# jlin_transceiver_prototype.net
KiCad netlist of a schematic drawn in Altium Designer
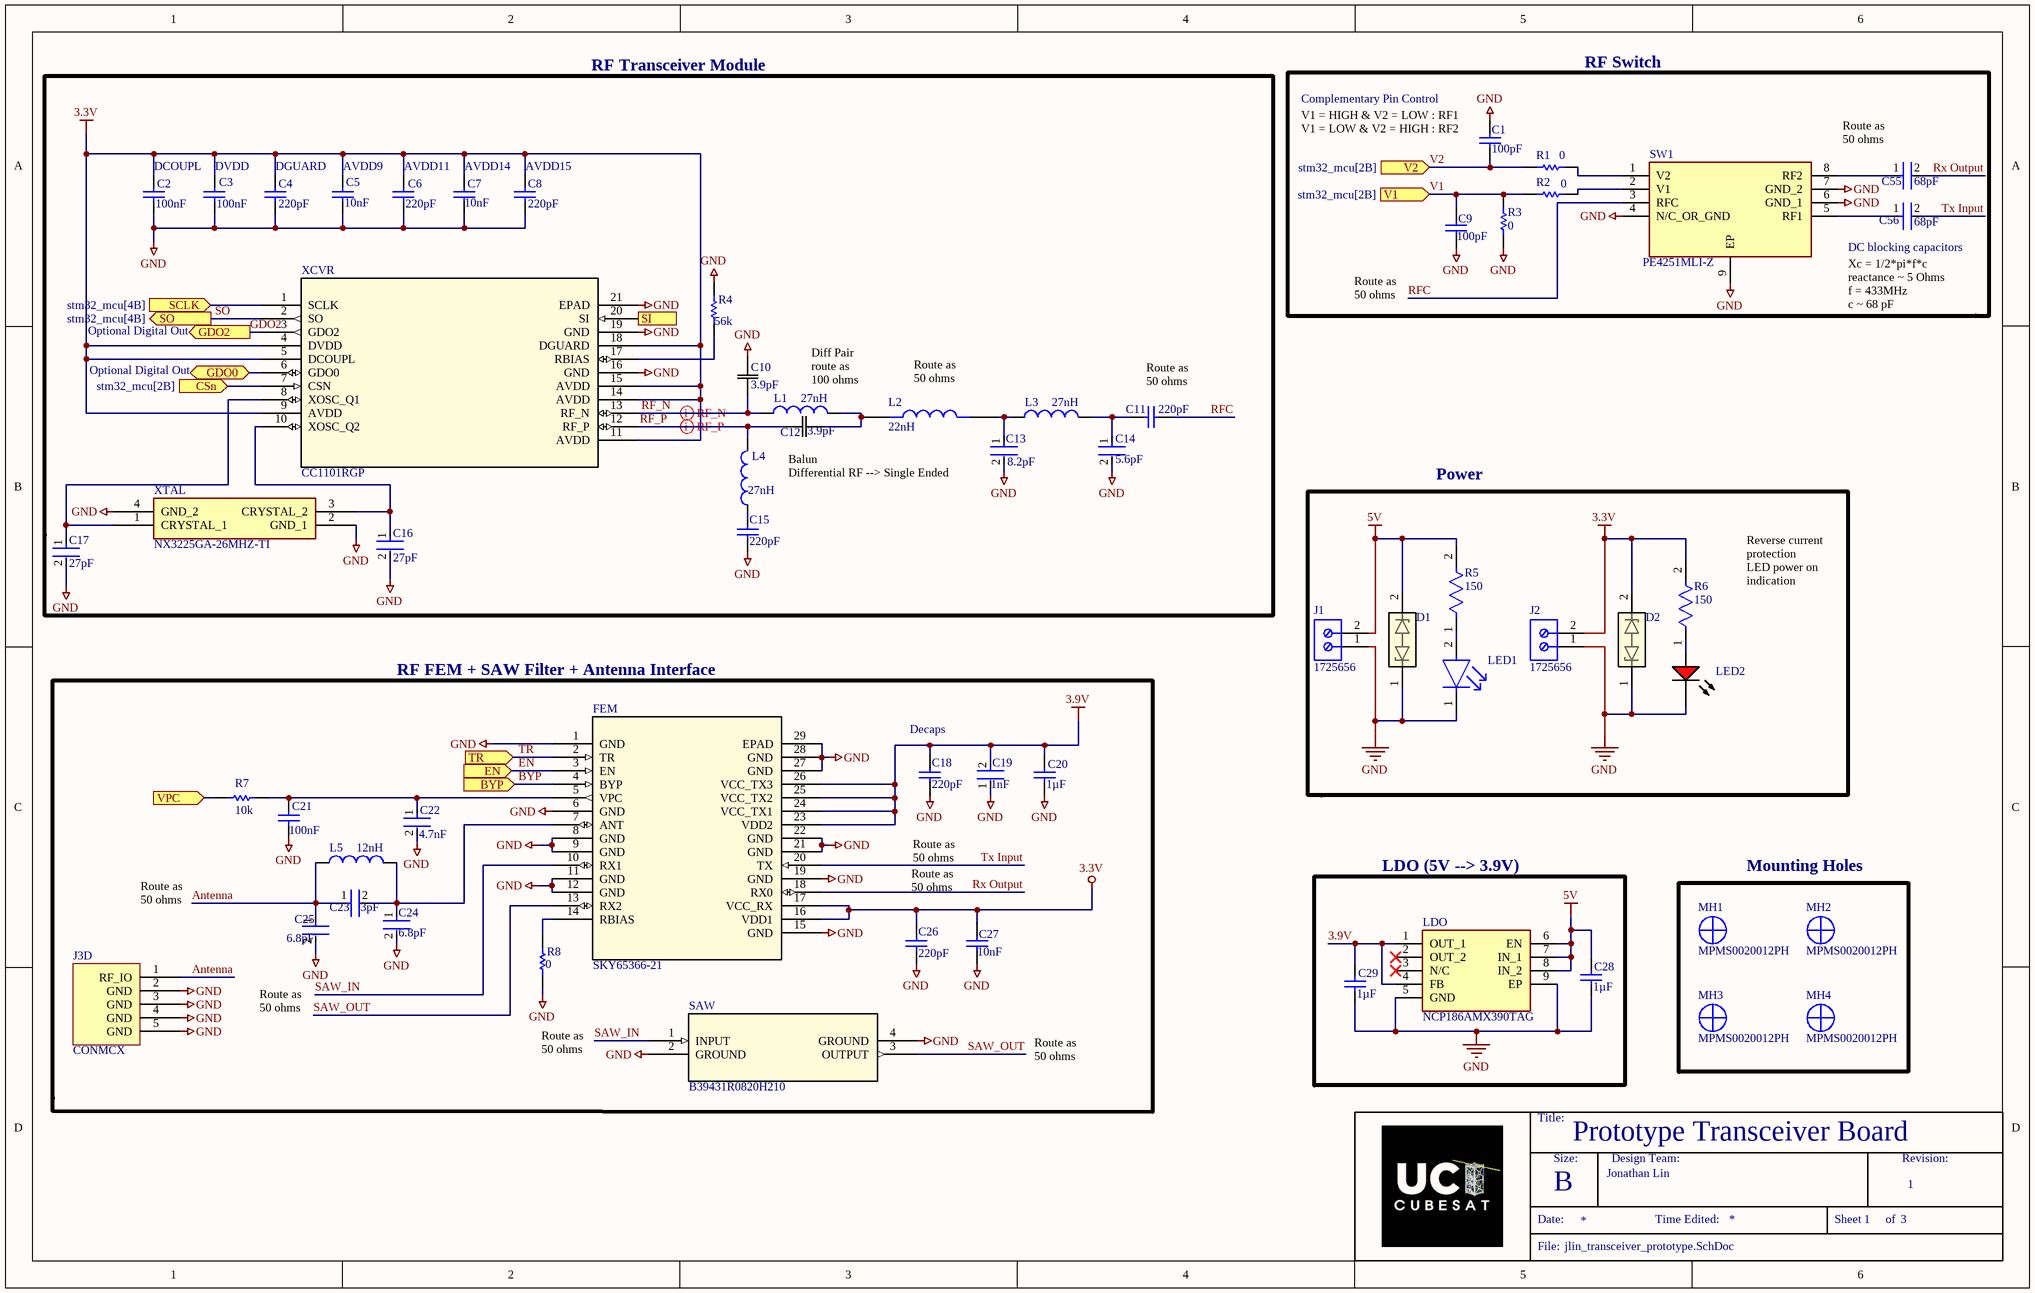
[diagram p0: jlin_transceiver_prototype.SchDoc]

(export (version "E")
  (design (tool "Eeschema 10.0.6"))
  (components
    (comp (ref "C1")
      (value "100pF")
      (footprint "CAPC2013X70X45LL10T25")
      (fields (field (name "Comment") "GRM2165C1H101JA01D"))
      (libsource (lib "University of California Irvine") (part "CAP"))
    )
    (comp (ref "C2")
      (value "100nF")
      (footprint "CAPC2013X135X45ML10T25")
      (fields (field (name "Comment") "GRM21BR72A104KAC4L"))
      (libsource (lib "University of California Irvine") (part "CAP"))
    )
    (comp (ref "C3")
      (value "100nF")
      (footprint "CAPC2013X135X45ML10T25")
      (fields (field (name "Comment") "GRM21BR72A104KAC4L"))
      (libsource (lib "University of California Irvine") (part "CAP"))
    )
    (comp (ref "C4")
      (value "220pF")
      (footprint "CAPC2013X70X45LL10T25")
      (fields (field (name "Comment") "GRM2165C1H221JA01D"))
      (libsource (lib "University of California Irvine") (part "CAP"))
    )
    (comp (ref "C5")
      (value "10nF")
      (footprint "CAPC2013X135X45ML10T25")
      (fields (field (name "Comment") "GRM21BR72A103KA01K"))
      (libsource (lib "University of California Irvine") (part "CAP"))
    )
    (comp (ref "C6")
      (value "220pF")
      (footprint "CAPC2013X70X45LL10T25")
      (fields (field (name "Comment") "GRM2165C1H221JA01D"))
      (libsource (lib "University of California Irvine") (part "CAP"))
    )
    (comp (ref "C7")
      (value "10nF")
      (footprint "CAPC2013X135X45ML10T25")
      (fields (field (name "Comment") "GRM21BR72A103KA01K"))
      (libsource (lib "University of California Irvine") (part "CAP"))
    )
    (comp (ref "C8")
      (value "220pF")
      (footprint "CAPC2013X70X45LL10T25")
      (fields (field (name "Comment") "GRM2165C1H221JA01D"))
      (libsource (lib "University of California Irvine") (part "CAP"))
    )
    (comp (ref "C9")
      (value "100pF")
      (footprint "CAPC2013X70X45LL10T25")
      (fields (field (name "Comment") "GRM2165C1H101JA01D"))
      (libsource (lib "University of California Irvine") (part "CAP"))
    )
    (comp (ref "C10")
      (value "3.9pF")
      (footprint "CAP_CC0805_YAG")
      (description "3.9 pF ±0.25pF 50V Ceramic Capacitor C0G, NP0 0805 (2012 Metric)")
      (fields (field (name "Comment") "CC0805CRNPO9BN3R9"))
      (libsource (lib "University of California Irvine") (part "CC0805CRNPO9BN3R9"))
    )
    (comp (ref "C11")
      (value "220pF")
      (footprint "CAPC2013X70X45LL10T25")
      (fields (field (name "Comment") "GRM2165C1H221JA01D"))
      (libsource (lib "University of California Irvine") (part "CAP"))
    )
    (comp (ref "C12")
      (value "3.9pF")
      (footprint "CAP_CC0805_YAG")
      (description "3.9 pF ±0.25pF 50V Ceramic Capacitor C0G, NP0 0805 (2012 Metric)")
      (fields (field (name "Comment") "CC0805CRNPO9BN3R9"))
      (libsource (lib "University of California Irvine") (part "CC0805CRNPO9BN3R9"))
    )
    (comp (ref "C13")
      (value "8.2pF")
      (footprint "FP-0805-L_2_01_0_2-W_1_25-MFG")
      (description "Cap Cer 8.2PF 100V C0G/NP0 0805")
      (fields (field (name "Comment") "KGM21BCG2A8R2DT"))
      (libsource (lib "University of California Irvine") (part "02cd4be3c70576c341d710602a673aa"))
    )
    (comp (ref "C14")
      (value "5.6pF")
      (footprint "FP-C0805C-DN-IPC_A")
      (fields (field (name "Comment") "C0805C569C5GACTU"))
      (libsource (lib "University of California Irvine") (part "b4654b650e69147ec39a6b967a45e02"))
    )
    (comp (ref "C15")
      (value "220pF")
      (footprint "CAPC2013X70X45LL10T25")
      (fields (field (name "Comment") "GRM2165C1H221JA01D"))
      (libsource (lib "University of California Irvine") (part "CAP"))
    )
    (comp (ref "C16")
      (value "27pF")
      (footprint "FP-GRM21A-0_2-IPC_B")
      (fields (field (name "Comment") "GRM21A5C2E270JW01D"))
      (libsource (lib "University of California Irvine") (part "02cd4be3c70576c341d710602a673aa"))
    )
    (comp (ref "C17")
      (value "27pF")
      (footprint "FP-GRM21A-0_2-IPC_B")
      (fields (field (name "Comment") "GRM21A5C2E270JW01D"))
      (libsource (lib "University of California Irvine") (part "02cd4be3c70576c341d710602a673aa"))
    )
    (comp (ref "C18")
      (value "220pF")
      (footprint "CAPC2013X70X45LL10T25")
      (fields (field (name "Comment") "GRM2165C1H221JA01D"))
      (libsource (lib "University of California Irvine") (part "CAP"))
    )
    (comp (ref "C19")
      (value "1nF")
      (footprint "FP-GRM216-0_1-IPC_B")
      (fields (field (name "Comment") "GRM2165C2A102JA01D"))
      (libsource (lib "University of California Irvine") (part "236180d848d6139a670b325ea6854c9"))
    )
    (comp (ref "C20")
      (value "1µF")
      (footprint "CAPC2013X135X45LL10T25")
      (fields (field (name "Comment") "GRM21BR71C105KA01L"))
      (libsource (lib "University of California Irvine") (part "CAP-NP-2"))
    )
    (comp (ref "C21")
      (value "100nF")
      (footprint "CAPC2013X135X45ML10T25")
      (fields (field (name "Comment") "GRM21BR72A104KAC4L"))
      (libsource (lib "University of California Irvine") (part "CAP"))
    )
    (comp (ref "C22")
      (value "4.7nF")
      (footprint "FP-GRM219-0_1-MFG")
      (fields (field (name "Comment") "GRM2195C1H472JA01D"))
      (libsource (lib "University of California Irvine") (part "02cd4be3c70576c341d710602a673aa"))
    )
    (comp (ref "C23")
      (value "3pF")
      (footprint "FP-C0805C-DN-IPC_A")
      (fields (field (name "Comment") "C0805C309C5GACTU"))
      (libsource (lib "University of California Irvine") (part "b4654b650e69147ec39a6b967a45e02"))
    )
    (comp (ref "C24")
      (value "6.8pF")
      (footprint "FP-GQM219-0_15-MFG")
      (fields (field (name "Comment") "GQM2195C2E6R8BB12D"))
      (libsource (lib "University of California Irvine") (part "b4654b650e69147ec39a6b967a45e02"))
    )
    (comp (ref "C25")
      (value "6.8pF")
      (footprint "FP-GQM219-0_15-MFG")
      (fields (field (name "Comment") "GQM2195C2E6R8BB12D"))
      (libsource (lib "University of California Irvine") (part "b4654b650e69147ec39a6b967a45e02"))
    )
    (comp (ref "C26")
      (value "220pF")
      (footprint "CAPC2013X70X45LL10T25")
      (fields (field (name "Comment") "GRM2165C1H221JA01D"))
      (libsource (lib "University of California Irvine") (part "CAP"))
    )
    (comp (ref "C27")
      (value "10nF")
      (footprint "CAPC2013X135X45ML10T25")
      (fields (field (name "Comment") "GRM21BR72A103KA01K"))
      (libsource (lib "University of California Irvine") (part "CAP"))
    )
    (comp (ref "C28")
      (value "1µF")
      (footprint "CAPC2013X135X45LL10T25")
      (fields (field (name "Comment") "GRM21BR71C105KA01L"))
      (libsource (lib "University of California Irvine") (part "CAP-NP-2"))
    )
    (comp (ref "C29")
      (value "1µF")
      (footprint "CAPC2013X135X45LL10T25")
      (fields (field (name "Comment") "GRM21BR71C105KA01L"))
      (libsource (lib "University of California Irvine") (part "CAP-NP-2"))
    )
    (comp (ref "C55")
      (value "68pF")
      (footprint "FP-GRM21A-0_2-IPC_B")
      (fields (field (name "Comment") "GRM21A5C2E680JW01D"))
      (libsource (lib "University of California Irvine") (part "02cd4be3c70576c341d710602a673aa"))
    )
    (comp (ref "C56")
      (value "68pF")
      (footprint "FP-GRM21A-0_2-IPC_B")
      (fields (field (name "Comment") "GRM21A5C2E680JW01D"))
      (libsource (lib "University of California Irvine") (part "02cd4be3c70576c341d710602a673aa"))
    )
    (comp (ref "D1")
      (value "PESD3V3Z1BCSFYL")
      (footprint "SOD962-2_DSN0603-2_NEX")
      (description "PESD3V3Zxx: 6.8 V 15 A 0.45 pF Bidirectional ESD Protection Diode - DSN0603-2")
      (libsource (lib "University of California Irvine") (part "PESD3V3Z1BCSFYL-Symbol-1"))
    )
    (comp (ref "D2")
      (value "PESD3V3Z1BCSFYL")
      (footprint "SOD962-2_DSN0603-2_NEX")
      (description "PESD3V3Zxx: 6.8 V 15 A 0.45 pF Bidirectional ESD Protection Diode - DSN0603-2")
      (libsource (lib "University of California Irvine") (part "PESD3V3Z1BCSFYL-Symbol-1"))
    )
    (comp (ref "FEM")
      (value "SKY65366-21")
      (footprint "SKY65366-21-Footprint-1")
      (description "RF and Baseband Circuit")
      (libsource (lib "Jonathan Lin") (part "SKY65366-21-Symbol-1"))
    )
    (comp (ref "J1")
      (value "1725656")
      (footprint "PHOE-1725656-2")
      (description "Male Header, Pitch 2.54 mm, 1 x 2 Position, Height 9 mm, Tail Length 3.5 mm")
      (fields (field (name "MANUFACTURER") "Phoenix Contact"))
      (libsource (lib "Altium Content Vault") (part "CN-1P-F-TB2"))
    )
    (comp (ref "J2")
      (value "1725656")
      (footprint "PHOE-1725656-2")
      (description "Male Header, Pitch 2.54 mm, 1 x 2 Position, Height 9 mm, Tail Length 3.5 mm")
      (fields (field (name "MANUFACTURER") "Phoenix Contact"))
      (libsource (lib "Altium Content Vault") (part "CN-1P-F-TB2"))
    )
    (comp (ref "J3")
      (value "CONMCX")
      (footprint "CONMCX002-Footprint-1")
      (description "MCX Connector Right Angle Jack (Female), PCB Through-Hole Mount, Gold")
      (libsource (lib "University of California Irvine") (part "CONMCX002-Symbol-1"))
    )
    (comp (ref "L1")
      (value "27nH")
      (footprint "WE-MK_0805_L2W1.25H0.85")
      (description "Multilayer Inductor, 27Nh, 0.3A, 0805 Rohs Compliant: Yes")
      (fields (field (name "Comment") "7447880127"))
      (libsource (lib "University of California Irvine") (part "Inductor - 1"))
    )
    (comp (ref "L2")
      (value "22nH")
      (footprint "INDC2012X105N")
      (description "General Purpose Inductor, 0.022uH, 5%, 1 Element, Ceramic-Core, SMD, 0805")
      (fields (field (name "MF") "Abracon") (field (name "MP") "AIMC-0805-22NJ-T"))
      (libsource (lib "University of California Irvine") (part "AIMC-0805-22NJ-T"))
    )
    (comp (ref "L3")
      (value "27nH")
      (footprint "WE-MK_0805_L2W1.25H0.85")
      (description "Multilayer Inductor, 27Nh, 0.3A, 0805 Rohs Compliant: Yes")
      (fields (field (name "Comment") "7447880127"))
      (libsource (lib "University of California Irvine") (part "Inductor - 1"))
    )
    (comp (ref "L4")
      (value "27nH")
      (footprint "WE-MK_0805_L2W1.25H0.85")
      (description "Multilayer Inductor, 27Nh, 0.3A, 0805 Rohs Compliant: Yes")
      (fields (field (name "Comment") "7447880127"))
      (libsource (lib "University of California Irvine") (part "Inductor - 1"))
    )
    (comp (ref "L5")
      (value "12nH")
      (footprint "AIMC-0805_ABR")
      (description "General Purpose Inductor, 0.012uH, 5%, 1 Element, Ceramic-Core, SMD, 0805")
      (fields (field (name "TOLERANCE") "5%") (field (name "Comment") "AIMC-0805-12NJ-T"))
      (libsource (lib "University of California Irvine") (part "IND-2"))
    )
    (comp (ref "LDO")
      (value "NCP186AMX390TAG")
      (footprint "NCP186AMX330TAG")
      (description "Fixed Positive LDO Regulator, 3.9V, 0.13V Dropout, CMOS, PDSO8")
      (fields (field (name "MOUSER PART NUMBER") "863-NCP186AMX390TAG"))
      (libsource (lib "University of California Irvine") (part "NCP186AMX390TAG"))
    )
    (comp (ref "LED1")
      (value "LTST-C170KFKT")
      (footprint "FP-LTST-C170KFKT-MFG")
      (description "Single Color LED, Orange, Water Clear, 1.4mm")
      (libsource (lib "University of California Irvine") (part "8706943c75ba83719d021d2fdc84c58"))
    )
    (comp (ref "LED2")
      (value "LTST-C190KRKT")
      (footprint "LTST-C191KRKT_V")
      (description "LED Uni-Color Red, 62.5 mW, 25 mA, -30 to 85 degC, 2-Pin SMD, RoHS, Tape and Reel")
      (fields (field (name "POWER") "75mW") (field (name "MANUFACTURER") "Lite-On"))
      (libsource (lib "University of California Irvine") (part "LED-RED-AK-2"))
    )
    (comp (ref "MH1")
      (value "MPMS0020012PH")
      (footprint "BF-MPMS0020012PH")
      (description "Copper Pillar, M2 Screw")
      (fields (field (name "MANUFACTURER") "B&F Fastener Supply"))
      (libsource (lib "University of California Irvine") (part "BF-MPMS0020012PH"))
    )
    (comp (ref "MH2")
      (value "MPMS0020012PH")
      (footprint "BF-MPMS0020012PH")
      (description "Copper Pillar, M2 Screw")
      (fields (field (name "MANUFACTURER") "B&F Fastener Supply"))
      (libsource (lib "University of California Irvine") (part "BF-MPMS0020012PH"))
    )
    (comp (ref "MH3")
      (value "MPMS0020012PH")
      (footprint "BF-MPMS0020012PH")
      (description "Copper Pillar, M2 Screw")
      (fields (field (name "MANUFACTURER") "B&F Fastener Supply"))
      (libsource (lib "University of California Irvine") (part "BF-MPMS0020012PH"))
    )
    (comp (ref "MH4")
      (value "MPMS0020012PH")
      (footprint "BF-MPMS0020012PH")
      (description "Copper Pillar, M2 Screw")
      (fields (field (name "MANUFACTURER") "B&F Fastener Supply"))
      (libsource (lib "University of California Irvine") (part "BF-MPMS0020012PH"))
    )
    (comp (ref "R1")
      (value "0")
      (footprint "RESC2013X60X35ML10T20")
      (description "Chip Resistor, 0 Ohm, 0.125 W, -55 to 155 degC, 0805 (2012 Metric)")
      (fields (field (name "POWER") "125mW") (field (name "TOLERANCE") "5%"))
      (libsource (lib "University of California Irvine") (part "RES-2"))
    )
    (comp (ref "R2")
      (value "0")
      (footprint "RESC2013X60X35ML10T20")
      (description "Chip Resistor, 0 Ohm, 0.125 W, -55 to 155 degC, 0805 (2012 Metric)")
      (fields (field (name "POWER") "125mW") (field (name "TOLERANCE") "5%"))
      (libsource (lib "University of California Irvine") (part "RES-2"))
    )
    (comp (ref "R3")
      (value "0")
      (footprint "RESC2013X60X35ML10T20")
      (description "Chip Resistor, 0 Ohm, 0.125 W, -55 to 155 degC, 0805 (2012 Metric)")
      (fields (field (name "POWER") "125mW") (field (name "TOLERANCE") "5%"))
      (libsource (lib "University of California Irvine") (part "RES-2"))
    )
    (comp (ref "R4")
      (value "56k")
      (footprint "RESC2013X70X40NL20T20")
      (fields
        (field (name "POWER") "125mW")
        (field (name "TOLERANCE") "5%")
        (field (name "Comment") "ERJ-6GEYJ563V")
      )
      (libsource (lib "University of California Irvine") (part "RES"))
    )
    (comp (ref "R5")
      (value "150")
      (footprint "FP-CRCW1210-e3-IPC_C")
      (fields
        (field (name "POWER") "500mW")
        (field (name "TOLERANCE") "5%")
        (field (name "Comment") "CRCW1210150RJNEA")
      )
      (libsource (lib "University of California Irvine") (part "1029c3af85768c4190bb7ad29bc67b5"))
    )
    (comp (ref "R6")
      (value "150")
      (footprint "FP-CRCW1210-e3-IPC_C")
      (fields
        (field (name "POWER") "500mW")
        (field (name "TOLERANCE") "5%")
        (field (name "Comment") "CRCW1210150RJNEA")
      )
      (libsource (lib "University of California Irvine") (part "1029c3af85768c4190bb7ad29bc67b5"))
    )
    (comp (ref "R7")
      (value "10k")
      (footprint "RESC2013X60X35LL10T20")
      (fields
        (field (name "TOLERANCE") "1%")
        (field (name "POWER") "125mW")
        (field (name "Comment") "RC0805FR-0710KL")
      )
      (libsource (lib "University of California Irvine") (part "RES-2"))
    )
    (comp (ref "R8")
      (value "0")
      (footprint "RESC2013X60X35ML10T20")
      (description "Chip Resistor, 0 Ohm, 0.125 W, -55 to 155 degC, 0805 (2012 Metric)")
      (fields (field (name "POWER") "125mW") (field (name "TOLERANCE") "5%"))
      (libsource (lib "University of California Irvine") (part "RES-2"))
    )
    (comp (ref "SAW")
      (value "B39431R0820H210")
      (footprint "B39431R0820H210_QUA")
      (description "433.92MHz SAW Resonator50 Ohm -40°C ~ 125°C Surface Mount")
      (libsource (lib "University of California Irvine") (part "B39431R0820H210-Symbol-1"))
    )
    (comp (ref "SW1")
      (value "PE4251MLI-Z")
      (footprint "SOP65P490X106-9N")
      (description "SPDT, 10MHz Min, 3000MHz Max, 1 Func, 0.9dB Insertion Loss-Max, CMOS")
      (fields (field (name "MOUSER PART NUMBER") "81-PE4251MLI-Z"))
      (libsource (lib "University of California Irvine") (part "PE4251MLI-Z"))
    )
    (comp (ref "XCVR")
      (value "CC1101RGP")
      (footprint "CC1101RGP-Footprint-1")
      (description "RF and Baseband Circuit, PQCC20")
      (libsource (lib "Jonathan Lin") (part "CC1101RGP-Symbol-1"))
    )
    (comp (ref "XTAL")
      (value "NX3225GA-26MHZ-TI")
      (footprint "NX3225GA_NDK")
      (description "Crystal 26.0000MHZ 10PF SMD")
      (libsource (lib "University of California Irvine") (part "NX3225GA-26MHZ-TI-Symbol-1"))
    )
  )
  (nets
    (net (code "1") (name "/Antenna") (class "Default")
      (node (ref "C23") (pin "1") (pinfunction "1_1") (pintype "passive"))
      (node (ref "C25") (pin "1") (pinfunction "1_1") (pintype "passive"))
      (node (ref "J3") (pin "1") (pinfunction "RF_IO_1") (pintype "passive"))
      (node (ref "L5") (pin "1") (pinfunction "1_1") (pintype "passive"))
    )
    (net (code "2") (name "/BYP") (class "Default")
      (node (ref "FEM") (pin "4") (pinfunction "BYP_4") (pintype "input"))
    )
    (net (code "3") (name "/CSn") (class "Default")
      (node (ref "XCVR") (pin "7") (pinfunction "CSN_7") (pintype "input"))
    )
    (net (code "4") (name "/EN") (class "Default")
      (node (ref "FEM") (pin "3") (pinfunction "EN_3") (pintype "input"))
    )
    (net (code "5") (name "/GDO0") (class "Default")
      (node (ref "XCVR") (pin "6") (pinfunction "GDO0_6") (pintype "bidirectional"))
    )
    (net (code "6") (name "/GDO2") (class "Default")
      (node (ref "XCVR") (pin "3") (pinfunction "GDO2_3") (pintype "output"))
    )
    (net (code "7") (name "/RFC") (class "Default")
      (node (ref "C11") (pin "2") (pinfunction "2_2") (pintype "passive"))
      (node (ref "SW1") (pin "3") (pinfunction "RFC_3") (pintype "passive"))
    )
    (net (code "8") (name "/RF_N") (class "Default")
      (node (ref "C10") (pin "1") (pinfunction "1_1") (pintype "passive"))
      (node (ref "L1") (pin "1") (pinfunction "1_1") (pintype "passive"))
      (node (ref "XCVR") (pin "13") (pinfunction "RF_N_13") (pintype "bidirectional"))
    )
    (net (code "9") (name "/RF_P") (class "Default")
      (node (ref "C12") (pin "1") (pinfunction "1_1") (pintype "passive"))
      (node (ref "L4") (pin "2") (pinfunction "2_2") (pintype "passive"))
      (node (ref "XCVR") (pin "12") (pinfunction "RF_P_12") (pintype "bidirectional"))
    )
    (net (code "10") (name "/Rx Output") (class "Default")
      (node (ref "C55") (pin "2") (pinfunction "2_2") (pintype "passive"))
      (node (ref "FEM") (pin "18") (pinfunction "RX0_18") (pintype "bidirectional"))
    )
    (net (code "11") (name "/SAW_IN") (class "Default")
      (node (ref "FEM") (pin "10") (pinfunction "RX1_10") (pintype "bidirectional"))
      (node (ref "SAW") (pin "1") (pinfunction "INPUT_1") (pintype "input"))
    )
    (net (code "12") (name "/SAW_OUT") (class "Default")
      (node (ref "FEM") (pin "13") (pinfunction "RX2_13") (pintype "bidirectional"))
      (node (ref "SAW") (pin "3") (pinfunction "OUTPUT_3") (pintype "output"))
    )
    (net (code "13") (name "/SCLK") (class "Default")
      (node (ref "XCVR") (pin "1") (pinfunction "SCLK_1") (pintype "passive"))
    )
    (net (code "14") (name "/SI") (class "Default")
      (node (ref "XCVR") (pin "20") (pinfunction "SI_20") (pintype "input"))
    )
    (net (code "15") (name "/SO") (class "Default")
      (node (ref "XCVR") (pin "2") (pinfunction "SO_2") (pintype "output"))
    )
    (net (code "16") (name "/TR") (class "Default")
      (node (ref "FEM") (pin "2") (pinfunction "TR_2") (pintype "input"))
    )
    (net (code "17") (name "/Tx Input") (class "Default")
      (node (ref "C56") (pin "2") (pinfunction "2_2") (pintype "passive"))
      (node (ref "FEM") (pin "20") (pinfunction "TX_20") (pintype "input"))
    )
    (net (code "18") (name "/V1") (class "Default")
      (node (ref "C9") (pin "2") (pinfunction "2_2") (pintype "passive"))
      (node (ref "R2") (pin "1") (pinfunction "1_1") (pintype "passive"))
      (node (ref "R3") (pin "2") (pinfunction "2_2") (pintype "passive"))
    )
    (net (code "19") (name "/V2") (class "Default")
      (node (ref "C1") (pin "1") (pinfunction "1_1") (pintype "passive"))
      (node (ref "R1") (pin "1") (pinfunction "1_1") (pintype "passive"))
    )
    (net (code "20") (name "/VPC") (class "Default")
      (node (ref "R7") (pin "1") (pinfunction "1_1") (pintype "passive"))
    )
    (net (code "21") (name "3.3V") (class "Default")
      (node (ref "C2") (pin "2") (pinfunction "2_2") (pintype "passive"))
      (node (ref "C26") (pin "2") (pinfunction "2_2") (pintype "passive"))
      (node (ref "C27") (pin "2") (pinfunction "2_2") (pintype "passive"))
      (node (ref "C3") (pin "2") (pinfunction "2_2") (pintype "passive"))
      (node (ref "C4") (pin "2") (pinfunction "2_2") (pintype "passive"))
      (node (ref "C5") (pin "2") (pinfunction "2_2") (pintype "passive"))
      (node (ref "C6") (pin "2") (pinfunction "2_2") (pintype "passive"))
      (node (ref "C7") (pin "2") (pinfunction "2_2") (pintype "passive"))
      (node (ref "C8") (pin "2") (pinfunction "2_2") (pintype "passive"))
      (node (ref "D2") (pin "2") (pinfunction "2_2") (pintype "passive"))
      (node (ref "FEM") (pin "16") (pinfunction "VDD1_16") (pintype "power_in"))
      (node (ref "FEM") (pin "17") (pinfunction "VCC_RX_17") (pintype "power_in"))
      (node (ref "J2") (pin "2") (pinfunction "2_2") (pintype "passive"))
      (node (ref "R6") (pin "2") (pinfunction "2_2") (pintype "passive"))
      (node (ref "XCVR") (pin "11") (pinfunction "AVDD_11") (pintype "power_in"))
      (node (ref "XCVR") (pin "14") (pinfunction "AVDD_14") (pintype "power_in"))
      (node (ref "XCVR") (pin "15") (pinfunction "AVDD_15") (pintype "power_in"))
      (node (ref "XCVR") (pin "18") (pinfunction "DGUARD_18") (pintype "power_in"))
      (node (ref "XCVR") (pin "4") (pinfunction "DVDD_4") (pintype "power_in"))
      (node (ref "XCVR") (pin "5") (pinfunction "DCOUPL_5") (pintype "power_in"))
      (node (ref "XCVR") (pin "9") (pinfunction "AVDD_9") (pintype "power_in"))
    )
    (net (code "22") (name "3.9V") (class "Default")
      (node (ref "C18") (pin "2") (pinfunction "2_2") (pintype "passive"))
      (node (ref "C19") (pin "2") (pinfunction "2_2") (pintype "passive"))
      (node (ref "C20") (pin "2") (pinfunction "2_2") (pintype "passive"))
      (node (ref "C29") (pin "2") (pinfunction "2_2") (pintype "passive"))
      (node (ref "FEM") (pin "23") (pinfunction "VDD2_23") (pintype "power_in"))
      (node (ref "FEM") (pin "24") (pinfunction "VCC_TX1_24") (pintype "power_in"))
      (node (ref "FEM") (pin "25") (pinfunction "VCC_TX2_25") (pintype "power_in"))
      (node (ref "FEM") (pin "26") (pinfunction "VCC_TX3_26") (pintype "power_in"))
      (node (ref "LDO") (pin "1") (pinfunction "OUT_1_1") (pintype "passive"))
      (node (ref "LDO") (pin "4") (pinfunction "FB_4") (pintype "passive"))
    )
    (net (code "23") (name "5V") (class "Default")
      (node (ref "C28") (pin "2") (pinfunction "2_2") (pintype "passive"))
      (node (ref "D1") (pin "2") (pinfunction "2_2") (pintype "passive"))
      (node (ref "J1") (pin "2") (pinfunction "2_2") (pintype "passive"))
      (node (ref "LDO") (pin "6") (pinfunction "EN_6") (pintype "passive"))
      (node (ref "LDO") (pin "7") (pinfunction "IN_1_7") (pintype "passive"))
      (node (ref "LDO") (pin "8") (pinfunction "IN_2_8") (pintype "passive"))
      (node (ref "R5") (pin "2") (pinfunction "2_2") (pintype "passive"))
    )
    (net (code "24") (name "GND") (class "Default")
      (node (ref "C1") (pin "2") (pinfunction "2_2") (pintype "passive"))
      (node (ref "C10") (pin "2") (pinfunction "2_2") (pintype "passive"))
      (node (ref "C13") (pin "2") (pinfunction "2_2") (pintype "passive"))
      (node (ref "C14") (pin "2") (pinfunction "2_2") (pintype "passive"))
      (node (ref "C15") (pin "1") (pinfunction "1_1") (pintype "passive"))
      (node (ref "C16") (pin "2") (pinfunction "2_2") (pintype "passive"))
      (node (ref "C17") (pin "2") (pinfunction "2_2") (pintype "passive"))
      (node (ref "C18") (pin "1") (pinfunction "1_1") (pintype "passive"))
      (node (ref "C19") (pin "1") (pinfunction "1_1") (pintype "passive"))
      (node (ref "C2") (pin "1") (pinfunction "1_1") (pintype "passive"))
      (node (ref "C20") (pin "1") (pinfunction "1_1") (pintype "passive"))
      (node (ref "C21") (pin "1") (pinfunction "1_1") (pintype "passive"))
      (node (ref "C22") (pin "2") (pinfunction "2_2") (pintype "passive"))
      (node (ref "C24") (pin "2") (pinfunction "2_2") (pintype "passive"))
      (node (ref "C25") (pin "2") (pinfunction "2_2") (pintype "passive"))
      (node (ref "C26") (pin "1") (pinfunction "1_1") (pintype "passive"))
      (node (ref "C27") (pin "1") (pinfunction "1_1") (pintype "passive"))
      (node (ref "C28") (pin "1") (pinfunction "1_1") (pintype "passive"))
      (node (ref "C29") (pin "1") (pinfunction "1_1") (pintype "passive"))
      (node (ref "C3") (pin "1") (pinfunction "1_1") (pintype "passive"))
      (node (ref "C4") (pin "1") (pinfunction "1_1") (pintype "passive"))
      (node (ref "C5") (pin "1") (pinfunction "1_1") (pintype "passive"))
      (node (ref "C6") (pin "1") (pinfunction "1_1") (pintype "passive"))
      (node (ref "C7") (pin "1") (pinfunction "1_1") (pintype "passive"))
      (node (ref "C8") (pin "1") (pinfunction "1_1") (pintype "passive"))
      (node (ref "C9") (pin "1") (pinfunction "1_1") (pintype "passive"))
      (node (ref "D1") (pin "1") (pinfunction "1_1") (pintype "passive"))
      (node (ref "D2") (pin "1") (pinfunction "1_1") (pintype "passive"))
      (node (ref "FEM") (pin "1") (pinfunction "GND_1") (pintype "power_in"))
      (node (ref "FEM") (pin "11") (pinfunction "GND_11") (pintype "power_in"))
      (node (ref "FEM") (pin "12") (pinfunction "GND_12") (pintype "power_in"))
      (node (ref "FEM") (pin "15") (pinfunction "GND_15") (pintype "power_in"))
      (node (ref "FEM") (pin "19") (pinfunction "GND_19") (pintype "power_in"))
      (node (ref "FEM") (pin "21") (pinfunction "GND_21") (pintype "power_in"))
      (node (ref "FEM") (pin "22") (pinfunction "GND_22") (pintype "power_in"))
      (node (ref "FEM") (pin "27") (pinfunction "GND_27") (pintype "power_in"))
      (node (ref "FEM") (pin "28") (pinfunction "GND_28") (pintype "power_in"))
      (node (ref "FEM") (pin "29") (pinfunction "EPAD_29") (pintype "passive"))
      (node (ref "FEM") (pin "6") (pinfunction "GND_6") (pintype "power_in"))
      (node (ref "FEM") (pin "8") (pinfunction "GND_8") (pintype "power_in"))
      (node (ref "FEM") (pin "9") (pinfunction "GND_9") (pintype "power_in"))
      (node (ref "J1") (pin "1") (pinfunction "1_1") (pintype "passive"))
      (node (ref "J2") (pin "1") (pinfunction "1_1") (pintype "passive"))
      (node (ref "J3") (pin "2") (pinfunction "GND_2") (pintype "passive"))
      (node (ref "J3") (pin "3") (pinfunction "GND_3") (pintype "passive"))
      (node (ref "J3") (pin "4") (pinfunction "GND_4") (pintype "passive"))
      (node (ref "J3") (pin "5") (pinfunction "GND_5") (pintype "passive"))
      (node (ref "LDO") (pin "5") (pinfunction "GND_5") (pintype "passive"))
      (node (ref "LDO") (pin "9") (pinfunction "EP_9") (pintype "passive"))
      (node (ref "LED1") (pin "1") (pinfunction "C_1") (pintype "passive"))
      (node (ref "LED2") (pin "2") (pinfunction "K_2") (pintype "passive"))
      (node (ref "R3") (pin "1") (pinfunction "1_1") (pintype "passive"))
      (node (ref "R4") (pin "2") (pinfunction "2_2") (pintype "passive"))
      (node (ref "R8") (pin "1") (pinfunction "1_1") (pintype "passive"))
      (node (ref "SAW") (pin "2") (pinfunction "GROUND_2") (pintype "power_in"))
      (node (ref "SAW") (pin "4") (pinfunction "GROUND_4") (pintype "power_in"))
      (node (ref "SW1") (pin "4") (pinfunction "N/C_OR_GND_4") (pintype "passive"))
      (node (ref "SW1") (pin "6") (pinfunction "GND_1_6") (pintype "passive"))
      (node (ref "SW1") (pin "7") (pinfunction "GND_2_7") (pintype "passive"))
      (node (ref "SW1") (pin "9") (pinfunction "EP_9") (pintype "passive"))
      (node (ref "XCVR") (pin "16") (pinfunction "GND_16") (pintype "power_in"))
      (node (ref "XCVR") (pin "19") (pinfunction "GND_19") (pintype "power_in"))
      (node (ref "XCVR") (pin "21") (pinfunction "EPAD_21") (pintype "power_in"))
      (node (ref "XTAL") (pin "2") (pinfunction "GND_1_2") (pintype "passive"))
      (node (ref "XTAL") (pin "4") (pinfunction "GND_2_4") (pintype "passive"))
    )
    (net (code "25") (name "Net-(C11-Pad1)") (class "Default")
      (node (ref "C11") (pin "1") (pinfunction "1_1") (pintype "passive"))
      (node (ref "C14") (pin "1") (pinfunction "1_1") (pintype "passive"))
      (node (ref "L3") (pin "2") (pinfunction "2_2") (pintype "passive"))
    )
    (net (code "26") (name "Net-(C12-Pad2)") (class "Default")
      (node (ref "C12") (pin "2") (pinfunction "2_2") (pintype "passive"))
      (node (ref "L1") (pin "2") (pinfunction "2_2") (pintype "passive"))
      (node (ref "L2") (pin "1") (pinfunction "1_1") (pintype "passive"))
    )
    (net (code "27") (name "Net-(C13-Pad1)") (class "Default")
      (node (ref "C13") (pin "1") (pinfunction "1_1") (pintype "passive"))
      (node (ref "L2") (pin "2") (pinfunction "2_2") (pintype "passive"))
      (node (ref "L3") (pin "1") (pinfunction "1_1") (pintype "passive"))
    )
    (net (code "28") (name "Net-(C15-Pad2)") (class "Default")
      (node (ref "C15") (pin "2") (pinfunction "2_2") (pintype "passive"))
      (node (ref "L4") (pin "1") (pinfunction "1_1") (pintype "passive"))
    )
    (net (code "29") (name "Net-(FEM-ANT)") (class "Default")
      (node (ref "C23") (pin "2") (pinfunction "2_2") (pintype "passive"))
      (node (ref "C24") (pin "1") (pinfunction "1_1") (pintype "passive"))
      (node (ref "FEM") (pin "7") (pinfunction "ANT_7") (pintype "bidirectional"))
      (node (ref "L5") (pin "2") (pinfunction "2_2") (pintype "passive"))
    )
    (net (code "30") (name "Net-(FEM-RBIAS)") (class "Default")
      (node (ref "FEM") (pin "14") (pinfunction "RBIAS_14") (pintype "passive"))
      (node (ref "R8") (pin "2") (pinfunction "2_2") (pintype "passive"))
    )
    (net (code "31") (name "Net-(FEM-VPC)") (class "Default")
      (node (ref "C21") (pin "2") (pinfunction "2_2") (pintype "passive"))
      (node (ref "C22") (pin "1") (pinfunction "1_1") (pintype "passive"))
      (node (ref "FEM") (pin "5") (pinfunction "VPC_5") (pintype "output"))
      (node (ref "R7") (pin "2") (pinfunction "2_2") (pintype "passive"))
    )
    (net (code "32") (name "Net-(LED1-A)") (class "Default")
      (node (ref "LED1") (pin "2") (pinfunction "A_2") (pintype "passive"))
      (node (ref "R5") (pin "1") (pinfunction "1_1") (pintype "passive"))
    )
    (net (code "33") (name "Net-(LED2-A)") (class "Default")
      (node (ref "LED2") (pin "1") (pinfunction "A_1") (pintype "passive"))
      (node (ref "R6") (pin "1") (pinfunction "1_1") (pintype "passive"))
    )
    (net (code "34") (name "Net-(SW1-RF1)") (class "Default")
      (node (ref "C56") (pin "1") (pinfunction "1_1") (pintype "passive"))
      (node (ref "SW1") (pin "5") (pinfunction "RF1_5") (pintype "passive"))
    )
    (net (code "35") (name "Net-(SW1-RF2)") (class "Default")
      (node (ref "C55") (pin "1") (pinfunction "1_1") (pintype "passive"))
      (node (ref "SW1") (pin "8") (pinfunction "RF2_8") (pintype "passive"))
    )
    (net (code "36") (name "Net-(SW1-V1)") (class "Default")
      (node (ref "R2") (pin "2") (pinfunction "2_2") (pintype "passive"))
      (node (ref "SW1") (pin "2") (pinfunction "V1_2") (pintype "passive"))
    )
    (net (code "37") (name "Net-(SW1-V2)") (class "Default")
      (node (ref "R1") (pin "2") (pinfunction "2_2") (pintype "passive"))
      (node (ref "SW1") (pin "1") (pinfunction "V2_1") (pintype "passive"))
    )
    (net (code "38") (name "Net-(XCVR-RBIAS)") (class "Default")
      (node (ref "R4") (pin "1") (pinfunction "1_1") (pintype "passive"))
      (node (ref "XCVR") (pin "17") (pinfunction "RBIAS_17") (pintype "bidirectional"))
    )
    (net (code "39") (name "Net-(XCVR-XOSC_Q1)") (class "Default")
      (node (ref "C17") (pin "1") (pinfunction "1_1") (pintype "passive"))
      (node (ref "XCVR") (pin "8") (pinfunction "XOSC_Q1_8") (pintype "bidirectional"))
      (node (ref "XTAL") (pin "1") (pinfunction "CRYSTAL_1_1") (pintype "passive"))
    )
    (net (code "40") (name "Net-(XCVR-XOSC_Q2)") (class "Default")
      (node (ref "C16") (pin "1") (pinfunction "1_1") (pintype "passive"))
      (node (ref "XCVR") (pin "10") (pinfunction "XOSC_Q2_10") (pintype "bidirectional"))
      (node (ref "XTAL") (pin "3") (pinfunction "CRYSTAL_2_3") (pintype "passive"))
    )
    (net (code "41") (name "unconnected-(LDO-N{slash}C-Pad3)") (class "Default")
      (node (ref "LDO") (pin "3") (pinfunction "N/C_3") (pintype "passive+no_connect"))
    )
    (net (code "42") (name "unconnected-(LDO-OUT_2-Pad2)") (class "Default")
      (node (ref "LDO") (pin "2") (pinfunction "OUT_2_2") (pintype "passive+no_connect"))
    )
    (net (code "43") (name "unconnected-(MH1-Pad1)") (class "Default")
      (node (ref "MH1") (pin "1") (pinfunction "1_1") (pintype "passive"))
    )
    (net (code "44") (name "unconnected-(MH2-Pad1)") (class "Default")
      (node (ref "MH2") (pin "1") (pinfunction "1_1") (pintype "passive"))
    )
    (net (code "45") (name "unconnected-(MH3-Pad1)") (class "Default")
      (node (ref "MH3") (pin "1") (pinfunction "1_1") (pintype "passive"))
    )
    (net (code "46") (name "unconnected-(MH4-Pad1)") (class "Default")
      (node (ref "MH4") (pin "1") (pinfunction "1_1") (pintype "passive"))
    )
  )
)
